# lin_master_node.net
KiCad netlist of a schematic drawn in EAGLE
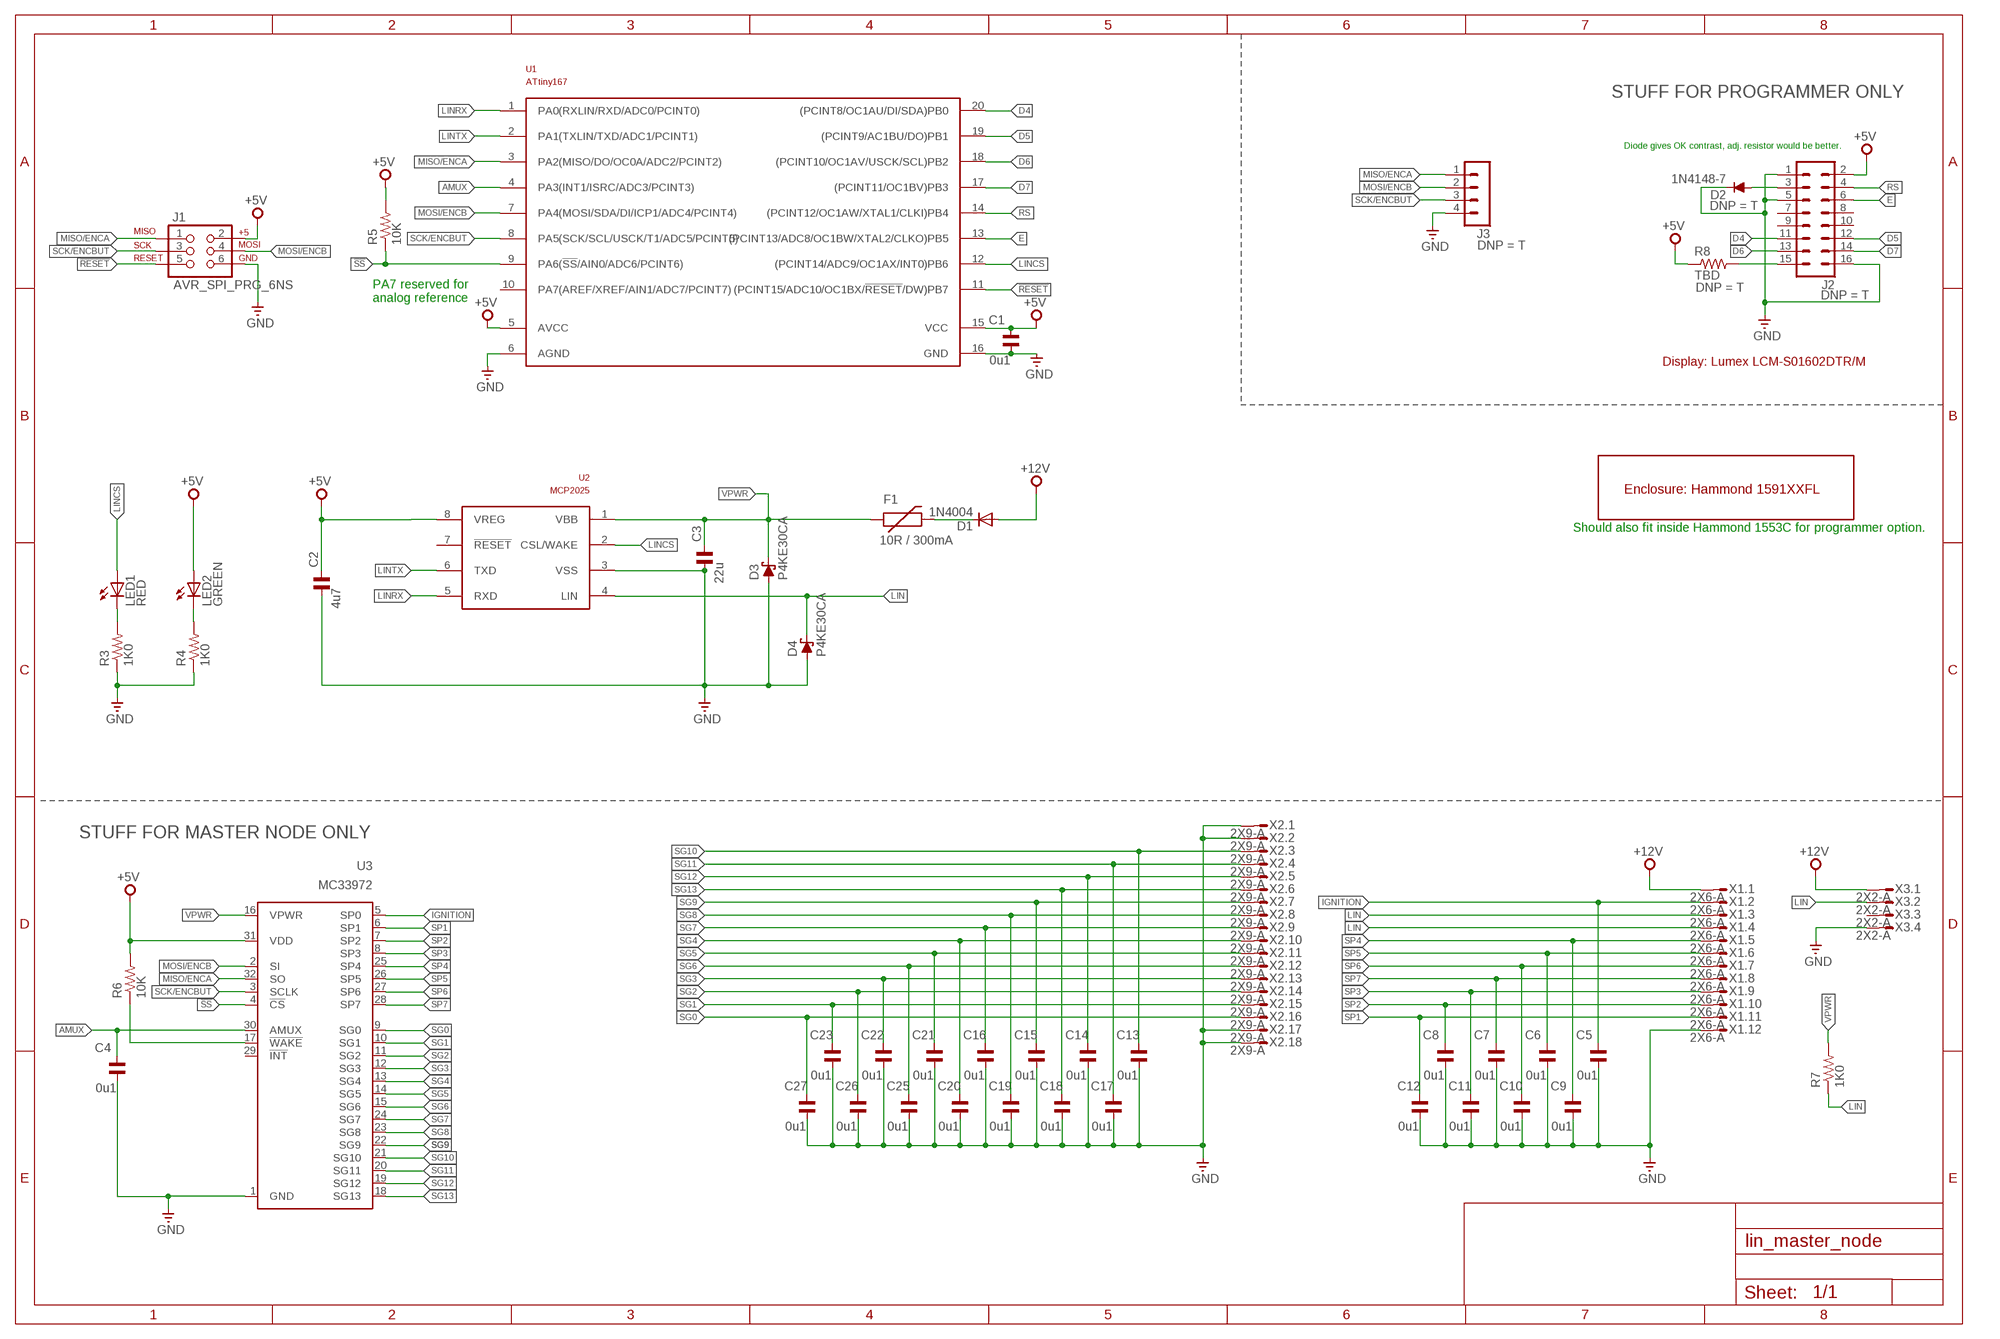
[diagram p0: schematic, sheet 1]

(export (version "E")
  (design (tool "Eeschema 10.0.6"))
  (components
    (comp (ref "C1")
      (value "0u1")
      (footprint "eagle-import:C050-024X044")
      (fields (field (name "PARTNO") "FK28X7R1H104K"))
      (libsource (lib "eagle-import") (part "C-EU050-024X044"))
    )
    (comp (ref "C2")
      (value "4u7")
      (footprint "eagle-import:C050-024X044")
      (fields (field (name "PARTNO") "FK28X5R0J475K"))
      (libsource (lib "eagle-import") (part "C-EU050-024X044"))
    )
    (comp (ref "C3")
      (value "22u")
      (footprint "eagle-import:C050-024X044")
      (fields (field (name "PARTNO") "FK22X5R1E226M"))
      (libsource (lib "eagle-import") (part "C-EU050-024X044"))
    )
    (comp (ref "C4")
      (value "0u1")
      (footprint "eagle-import:C050-024X044")
      (fields (field (name "PARTNO") "FK28X7R1H104K"))
      (libsource (lib "eagle-import") (part "C-EU050-024X044"))
    )
    (comp (ref "C5")
      (value "0u1")
      (footprint "eagle-import:C0603K")
      (fields (field (name "PARTNO") "C1608X7R1H104M080AA"))
      (libsource (lib "eagle-import") (part "C-EUC0603K"))
    )
    (comp (ref "C6")
      (value "0u1")
      (footprint "eagle-import:C0603K")
      (fields (field (name "PARTNO") "C1608X7R1H104M080AA"))
      (libsource (lib "eagle-import") (part "C-EUC0603K"))
    )
    (comp (ref "C7")
      (value "0u1")
      (footprint "eagle-import:C0603K")
      (fields (field (name "PARTNO") "C1608X7R1H104M080AA"))
      (libsource (lib "eagle-import") (part "C-EUC0603K"))
    )
    (comp (ref "C8")
      (value "0u1")
      (footprint "eagle-import:C0603K")
      (fields (field (name "PARTNO") "C1608X7R1H104M080AA"))
      (libsource (lib "eagle-import") (part "C-EUC0603K"))
    )
    (comp (ref "C9")
      (value "0u1")
      (footprint "eagle-import:C0603K")
      (fields (field (name "PARTNO") "C1608X7R1H104M080AA"))
      (libsource (lib "eagle-import") (part "C-EUC0603K"))
    )
    (comp (ref "C10")
      (value "0u1")
      (footprint "eagle-import:C0603K")
      (fields (field (name "PARTNO") "C1608X7R1H104M080AA"))
      (libsource (lib "eagle-import") (part "C-EUC0603K"))
    )
    (comp (ref "C11")
      (value "0u1")
      (footprint "eagle-import:C0603K")
      (fields (field (name "PARTNO") "C1608X7R1H104M080AA"))
      (libsource (lib "eagle-import") (part "C-EUC0603K"))
    )
    (comp (ref "C12")
      (value "0u1")
      (footprint "eagle-import:C0603K")
      (fields (field (name "PARTNO") "C1608X7R1H104M080AA"))
      (libsource (lib "eagle-import") (part "C-EUC0603K"))
    )
    (comp (ref "C13")
      (value "0u1")
      (footprint "eagle-import:C0603K")
      (fields (field (name "PARTNO") "C1608X7R1H104M080AA"))
      (libsource (lib "eagle-import") (part "C-EUC0603K"))
    )
    (comp (ref "C14")
      (value "0u1")
      (footprint "eagle-import:C0603K")
      (fields (field (name "PARTNO") "C1608X7R1H104M080AA"))
      (libsource (lib "eagle-import") (part "C-EUC0603K"))
    )
    (comp (ref "C15")
      (value "0u1")
      (footprint "eagle-import:C0603K")
      (fields (field (name "PARTNO") "C1608X7R1H104M080AA"))
      (libsource (lib "eagle-import") (part "C-EUC0603K"))
    )
    (comp (ref "C16")
      (value "0u1")
      (footprint "eagle-import:C0603K")
      (fields (field (name "PARTNO") "C1608X7R1H104M080AA"))
      (libsource (lib "eagle-import") (part "C-EUC0603K"))
    )
    (comp (ref "C17")
      (value "0u1")
      (footprint "eagle-import:C0603K")
      (fields (field (name "PARTNO") "C1608X7R1H104M080AA"))
      (libsource (lib "eagle-import") (part "C-EUC0603K"))
    )
    (comp (ref "C18")
      (value "0u1")
      (footprint "eagle-import:C0603K")
      (fields (field (name "PARTNO") "C1608X7R1H104M080AA"))
      (libsource (lib "eagle-import") (part "C-EUC0603K"))
    )
    (comp (ref "C19")
      (value "0u1")
      (footprint "eagle-import:C0603K")
      (fields (field (name "PARTNO") "C1608X7R1H104M080AA"))
      (libsource (lib "eagle-import") (part "C-EUC0603K"))
    )
    (comp (ref "C20")
      (value "0u1")
      (footprint "eagle-import:C0603K")
      (fields (field (name "PARTNO") "C1608X7R1H104M080AA"))
      (libsource (lib "eagle-import") (part "C-EUC0603K"))
    )
    (comp (ref "C21")
      (value "0u1")
      (footprint "eagle-import:C0603K")
      (fields (field (name "PARTNO") "C1608X7R1H104M080AA"))
      (libsource (lib "eagle-import") (part "C-EUC0603K"))
    )
    (comp (ref "C22")
      (value "0u1")
      (footprint "eagle-import:C0603K")
      (fields (field (name "PARTNO") "C1608X7R1H104M080AA"))
      (libsource (lib "eagle-import") (part "C-EUC0603K"))
    )
    (comp (ref "C23")
      (value "0u1")
      (footprint "eagle-import:C0603K")
      (fields (field (name "PARTNO") "C1608X7R1H104M080AA"))
      (libsource (lib "eagle-import") (part "C-EUC0603K"))
    )
    (comp (ref "C25")
      (value "0u1")
      (footprint "eagle-import:C0603K")
      (fields (field (name "PARTNO") "C1608X7R1H104M080AA"))
      (libsource (lib "eagle-import") (part "C-EUC0603K"))
    )
    (comp (ref "C26")
      (value "0u1")
      (footprint "eagle-import:C0603K")
      (fields (field (name "PARTNO") "C1608X7R1H104M080AA"))
      (libsource (lib "eagle-import") (part "C-EUC0603K"))
    )
    (comp (ref "C27")
      (value "0u1")
      (footprint "eagle-import:C0603K")
      (fields (field (name "PARTNO") "C1608X7R1H104M080AA"))
      (libsource (lib "eagle-import") (part "C-EUC0603K"))
    )
    (comp (ref "D1")
      (value "1N4004")
      (footprint "eagle-import:DO41-10")
      (fields (field (name "PARTNO") "1N4004-TP"))
      (libsource (lib "eagle-import") (part "1N4004"))
    )
    (comp (ref "D2")
      (value "1N4148-7")
      (footprint "eagle-import:DO35-7")
      (fields (field (name "DNP") "T") (field (name "PARTNO") "1N4148TA"))
      (libsource (lib "eagle-import") (part "1N4148-7"))
    )
    (comp (ref "D3")
      (value "P4KE30CA")
      (footprint "eagle-import:DO41-10")
      (libsource (lib "eagle-import") (part "P4KEXX"))
    )
    (comp (ref "D4")
      (value "P4KE30CA")
      (footprint "eagle-import:DO41-10")
      (libsource (lib "eagle-import") (part "P4KEXX"))
    )
    (comp (ref "F1")
      (value "10R / 300mA")
      (footprint "eagle-import:PTC")
      (fields (field (name "PARTNO") "CMF-RL10-0"))
      (libsource (lib "eagle-import") (part "PTCPTH"))
    )
    (comp (ref "J1")
      (value "AVR_SPI_PRG_6NS")
      (footprint "eagle-import:2X3-NS")
      (libsource (lib "eagle-import") (part "AVR_SPI_PRG_6NS"))
    )
    (comp (ref "J2")
      (value "MA08-2")
      (footprint "eagle-import:MA08-2")
      (fields (field (name "DNP") "T"))
      (libsource (lib "eagle-import") (part "MA08-2"))
    )
    (comp (ref "J3")
      (value "MA04-1")
      (footprint "eagle-import:MA04-1")
      (fields (field (name "DNP") "T"))
      (libsource (lib "eagle-import") (part "MA04-1"))
    )
    (comp (ref "LED1")
      (value "RED")
      (footprint "eagle-import:LED3MM")
      (fields (field (name "PARTNO") "C4SMF-RJS-CT0W0BB2"))
      (libsource (lib "eagle-import") (part "LED3MM"))
    )
    (comp (ref "LED2")
      (value "GREEN")
      (footprint "eagle-import:LED3MM")
      (fields (field (name "PARTNO") "C4SMF-GJS-CV0Y0792"))
      (libsource (lib "eagle-import") (part "LED3MM"))
    )
    (comp (ref "R3")
      (value "1K0")
      (footprint "eagle-import:0207_10")
      (fields (field (name "PARTNO") "CF14JT1K00"))
      (libsource (lib "eagle-import") (part "R-EU_0207/10"))
    )
    (comp (ref "R4")
      (value "1K0")
      (footprint "eagle-import:0207_10")
      (fields (field (name "PARTNO") "CF14JT1K00"))
      (libsource (lib "eagle-import") (part "R-EU_0207/10"))
    )
    (comp (ref "R5")
      (value "10K")
      (footprint "eagle-import:0207_10")
      (fields (field (name "PARTNO") "CF14JT10K0"))
      (libsource (lib "eagle-import") (part "R-EU_0207/10"))
    )
    (comp (ref "R6")
      (value "10K")
      (footprint "eagle-import:0207_10")
      (fields (field (name "PARTNO") "CF14JT10K0"))
      (libsource (lib "eagle-import") (part "R-EU_0207/10"))
    )
    (comp (ref "R7")
      (value "1K0")
      (footprint "eagle-import:0207_10")
      (fields (field (name "PARTNO") "CF14JT1K00"))
      (libsource (lib "eagle-import") (part "R-EU_0207/10"))
    )
    (comp (ref "R8")
      (value "TBD")
      (footprint "eagle-import:0207_10")
      (fields (field (name "DNP") "T"))
      (libsource (lib "eagle-import") (part "R-EU_0207/10"))
    )
    (comp (ref "U$1")
      (value "1591XXAFL")
      (footprint "eagle-import:1591XXAFL")
      (fields (field (name "PARTNO") "1591XXAFLBK"))
      (libsource (lib "eagle-import") (part "1591XXAFL"))
    )
    (comp (ref "U1")
      (value "ATtiny167")
      (footprint "eagle-import:SO20W")
      (fields (field (name "PARTNO") "ATTINY167-SU"))
      (libsource (lib "eagle-import") (part "ATTINY167"))
    )
    (comp (ref "U2")
      (value "MCP2025")
      (footprint "eagle-import:SO08")
      (fields (field (name "PARTNO") "MCP2025-500E/SN"))
      (libsource (lib "eagle-import") (part "MCP2025"))
    )
    (comp (ref "U3")
      (value "MC33972")
      (footprint "eagle-import:SOIC32W")
      (fields (field (name "PARTNO") "MC33972ATEW"))
      (libsource (lib "eagle-import") (part "MC33972"))
    )
    (comp (ref "X1")
      (value "2X6-A")
      (footprint "eagle-import:4-794618-2")
      (fields (field (name "PARTNO") "4-794618-2"))
      (libsource (lib "eagle-import") (part "2X6-A"))
    )
    (comp (ref "X2")
      (value "2X9-A")
      (footprint "eagle-import:4-794618-8")
      (fields (field (name "PARTNO") "4-794618-8"))
      (libsource (lib "eagle-import") (part "2X9-A"))
    )
    (comp (ref "X3")
      (value "2X2-A")
      (footprint "eagle-import:3-794618-4")
      (fields (field (name "PARTNO") "3-794618-4"))
      (libsource (lib "eagle-import") (part "2X2-A"))
    )
  )
  (nets
    (net (code "1") (name "+5V") (class "Default")
      (node (ref "C1") (pin "1") (pinfunction "1_1") (pintype "passive"))
      (node (ref "C2") (pin "1") (pinfunction "1_1") (pintype "passive"))
      (node (ref "J1") (pin "2") (pinfunction "2_2") (pintype "passive"))
      (node (ref "J2") (pin "2") (pinfunction "2_2") (pintype "passive"))
      (node (ref "LED2") (pin "A") (pinfunction "A_A") (pintype "passive"))
      (node (ref "R5") (pin "2") (pinfunction "2_2") (pintype "passive"))
      (node (ref "R6") (pin "2") (pinfunction "2_2") (pintype "passive"))
      (node (ref "R8") (pin "1") (pinfunction "1_1") (pintype "passive"))
      (node (ref "U1") (pin "15") (pinfunction "VCC_15") (pintype "power_in"))
      (node (ref "U1") (pin "5") (pinfunction "AVCC_5") (pintype "power_in"))
      (node (ref "U2") (pin "8") (pinfunction "VREG_8") (pintype "power_in"))
      (node (ref "U3") (pin "31") (pinfunction "VDD_31") (pintype "power_in"))
    )
    (net (code "2") (name "+12V") (class "Default")
      (node (ref "D1") (pin "A") (pinfunction "A_A") (pintype "passive"))
      (node (ref "X1") (pin "1") (pinfunction "S_1") (pintype "passive"))
      (node (ref "X3") (pin "1") (pinfunction "S_1") (pintype "passive"))
    )
    (net (code "3") (name "/~{RESET}") (class "Default")
      (node (ref "J1") (pin "5") (pinfunction "5_5") (pintype "passive"))
      (node (ref "U1") (pin "11") (pinfunction "(PCINT15/ADC10/OC1BX/~{RESET}/DW)PB7_11") (pintype "bidirectional"))
    )
    (net (code "4") (name "/~{SS}") (class "Default")
      (node (ref "R5") (pin "1") (pinfunction "1_1") (pintype "passive"))
      (node (ref "U1") (pin "9") (pinfunction "PA6(~{SS}/AIN0/ADC6/PCINT6)_9") (pintype "bidirectional"))
      (node (ref "U3") (pin "4") (pinfunction "~{CS}_4") (pintype "input"))
    )
    (net (code "5") (name "AMUX") (class "Default")
      (node (ref "C4") (pin "1") (pinfunction "1_1") (pintype "passive"))
      (node (ref "U1") (pin "4") (pinfunction "PA3(INT1/ISRC/ADC3/PCINT3)_4") (pintype "bidirectional"))
      (node (ref "U3") (pin "30") (pinfunction "AMUX_30") (pintype "output"))
    )
    (net (code "6") (name "D4") (class "Default")
      (node (ref "J2") (pin "11") (pinfunction "11_11") (pintype "passive"))
      (node (ref "U1") (pin "20") (pinfunction "(PCINT8/OC1AU/DI/SDA)PB0_20") (pintype "bidirectional"))
    )
    (net (code "7") (name "D5") (class "Default")
      (node (ref "J2") (pin "12") (pinfunction "12_12") (pintype "passive"))
      (node (ref "U1") (pin "19") (pinfunction "(PCINT9/AC1BU/DO)PB1_19") (pintype "bidirectional"))
    )
    (net (code "8") (name "D6") (class "Default")
      (node (ref "J2") (pin "13") (pinfunction "13_13") (pintype "passive"))
      (node (ref "U1") (pin "18") (pinfunction "(PCINT10/OC1AV/USCK/SCL)PB2_18") (pintype "bidirectional"))
    )
    (net (code "9") (name "D7") (class "Default")
      (node (ref "J2") (pin "14") (pinfunction "14_14") (pintype "passive"))
      (node (ref "U1") (pin "17") (pinfunction "(PCINT11/OC1BV)PB3_17") (pintype "bidirectional"))
    )
    (net (code "10") (name "E") (class "Default")
      (node (ref "J2") (pin "6") (pinfunction "6_6") (pintype "passive"))
      (node (ref "U1") (pin "13") (pinfunction "(PCINT13/ADC8/OC1BW/XTAL2/CLKO)PB5_13") (pintype "bidirectional"))
    )
    (net (code "11") (name "GND") (class "Default")
      (node (ref "C1") (pin "2") (pinfunction "2_2") (pintype "passive"))
      (node (ref "C10") (pin "2") (pinfunction "2_2") (pintype "passive"))
      (node (ref "C11") (pin "2") (pinfunction "2_2") (pintype "passive"))
      (node (ref "C12") (pin "2") (pinfunction "2_2") (pintype "passive"))
      (node (ref "C13") (pin "2") (pinfunction "2_2") (pintype "passive"))
      (node (ref "C14") (pin "2") (pinfunction "2_2") (pintype "passive"))
      (node (ref "C15") (pin "2") (pinfunction "2_2") (pintype "passive"))
      (node (ref "C16") (pin "2") (pinfunction "2_2") (pintype "passive"))
      (node (ref "C17") (pin "2") (pinfunction "2_2") (pintype "passive"))
      (node (ref "C18") (pin "2") (pinfunction "2_2") (pintype "passive"))
      (node (ref "C19") (pin "2") (pinfunction "2_2") (pintype "passive"))
      (node (ref "C2") (pin "2") (pinfunction "2_2") (pintype "passive"))
      (node (ref "C20") (pin "2") (pinfunction "2_2") (pintype "passive"))
      (node (ref "C21") (pin "2") (pinfunction "2_2") (pintype "passive"))
      (node (ref "C22") (pin "2") (pinfunction "2_2") (pintype "passive"))
      (node (ref "C23") (pin "2") (pinfunction "2_2") (pintype "passive"))
      (node (ref "C25") (pin "2") (pinfunction "2_2") (pintype "passive"))
      (node (ref "C26") (pin "2") (pinfunction "2_2") (pintype "passive"))
      (node (ref "C27") (pin "2") (pinfunction "2_2") (pintype "passive"))
      (node (ref "C3") (pin "2") (pinfunction "2_2") (pintype "passive"))
      (node (ref "C4") (pin "2") (pinfunction "2_2") (pintype "passive"))
      (node (ref "C5") (pin "2") (pinfunction "2_2") (pintype "passive"))
      (node (ref "C6") (pin "2") (pinfunction "2_2") (pintype "passive"))
      (node (ref "C7") (pin "2") (pinfunction "2_2") (pintype "passive"))
      (node (ref "C8") (pin "2") (pinfunction "2_2") (pintype "passive"))
      (node (ref "C9") (pin "2") (pinfunction "2_2") (pintype "passive"))
      (node (ref "D2") (pin "C") (pinfunction "C_C") (pintype "passive"))
      (node (ref "D3") (pin "A") (pinfunction "A_A") (pintype "passive"))
      (node (ref "D4") (pin "A") (pinfunction "A_A") (pintype "passive"))
      (node (ref "J1") (pin "6") (pinfunction "6_6") (pintype "passive"))
      (node (ref "J2") (pin "1") (pinfunction "1_1") (pintype "passive"))
      (node (ref "J2") (pin "16") (pinfunction "16_16") (pintype "passive"))
      (node (ref "J2") (pin "5") (pinfunction "5_5") (pintype "passive"))
      (node (ref "J3") (pin "4") (pinfunction "4_4") (pintype "passive"))
      (node (ref "R3") (pin "1") (pinfunction "1_1") (pintype "passive"))
      (node (ref "R4") (pin "1") (pinfunction "1_1") (pintype "passive"))
      (node (ref "U1") (pin "16") (pinfunction "GND_16") (pintype "power_in"))
      (node (ref "U1") (pin "6") (pinfunction "AGND_6") (pintype "power_in"))
      (node (ref "U2") (pin "3") (pinfunction "VSS_3") (pintype "power_in"))
      (node (ref "U3") (pin "1") (pinfunction "GND_1") (pintype "power_in"))
      (node (ref "X1") (pin "12") (pinfunction "S_12") (pintype "passive"))
      (node (ref "X2") (pin "1") (pinfunction "S_1") (pintype "passive"))
      (node (ref "X2") (pin "17") (pinfunction "S_17") (pintype "passive"))
      (node (ref "X2") (pin "18") (pinfunction "S_18") (pintype "passive"))
      (node (ref "X2") (pin "2") (pinfunction "S_2") (pintype "passive"))
      (node (ref "X3") (pin "4") (pinfunction "S_4") (pintype "passive"))
    )
    (net (code "12") (name "IGNITION") (class "Default")
      (node (ref "C5") (pin "1") (pinfunction "1_1") (pintype "passive"))
      (node (ref "U3") (pin "5") (pinfunction "SP0_5") (pintype "input"))
      (node (ref "X1") (pin "2") (pinfunction "S_2") (pintype "passive"))
    )
    (net (code "13") (name "LIN") (class "Default")
      (node (ref "D4") (pin "C") (pinfunction "C_C") (pintype "passive"))
      (node (ref "R7") (pin "1") (pinfunction "1_1") (pintype "passive"))
      (node (ref "U2") (pin "4") (pinfunction "LIN_4") (pintype "bidirectional"))
      (node (ref "X1") (pin "3") (pinfunction "S_3") (pintype "passive"))
      (node (ref "X1") (pin "4") (pinfunction "S_4") (pintype "passive"))
      (node (ref "X3") (pin "2") (pinfunction "S_2") (pintype "passive"))
    )
    (net (code "14") (name "LINCS") (class "Default")
      (node (ref "LED1") (pin "A") (pinfunction "A_A") (pintype "passive"))
      (node (ref "U1") (pin "12") (pinfunction "(PCINT14/ADC9/OC1AX/INT0)PB6_12") (pintype "bidirectional"))
      (node (ref "U2") (pin "2") (pinfunction "CSL/WAKE_2") (pintype "input"))
    )
    (net (code "15") (name "LINRX") (class "Default")
      (node (ref "U1") (pin "1") (pinfunction "PA0(RXLIN/RXD/ADC0/PCINT0)_1") (pintype "bidirectional"))
      (node (ref "U2") (pin "5") (pinfunction "RXD_5") (pintype "output"))
    )
    (net (code "16") (name "LINTX") (class "Default")
      (node (ref "U1") (pin "2") (pinfunction "PA1(TXLIN/TXD/ADC1/PCINT1)_2") (pintype "bidirectional"))
      (node (ref "U2") (pin "6") (pinfunction "TXD_6") (pintype "input"))
    )
    (net (code "17") (name "MISO{slash}ENCA") (class "Default")
      (node (ref "J1") (pin "1") (pinfunction "1_1") (pintype "passive"))
      (node (ref "J3") (pin "1") (pinfunction "1_1") (pintype "passive"))
      (node (ref "U1") (pin "3") (pinfunction "PA2(MISO/DO/OC0A/ADC2/PCINT2)_3") (pintype "bidirectional"))
      (node (ref "U3") (pin "32") (pinfunction "SO_32") (pintype "output"))
    )
    (net (code "18") (name "MOSI{slash}ENCB") (class "Default")
      (node (ref "J1") (pin "4") (pinfunction "4_4") (pintype "passive"))
      (node (ref "J3") (pin "2") (pinfunction "2_2") (pintype "passive"))
      (node (ref "U1") (pin "7") (pinfunction "PA4(MOSI/SDA/DI/ICP1/ADC4/PCINT4)_7") (pintype "bidirectional"))
      (node (ref "U3") (pin "2") (pinfunction "SI_2") (pintype "input"))
    )
    (net (code "19") (name "Net-(D2-PadA)") (class "Default")
      (node (ref "D2") (pin "A") (pinfunction "A_A") (pintype "passive"))
      (node (ref "J2") (pin "3") (pinfunction "3_3") (pintype "passive"))
    )
    (net (code "20") (name "Net-(F1-2)") (class "Default")
      (node (ref "D1") (pin "C") (pinfunction "C_C") (pintype "passive"))
      (node (ref "F1") (pin "P$2") (pinfunction "2_P$2") (pintype "bidirectional"))
    )
    (net (code "21") (name "Net-(J2-Pad15)") (class "Default")
      (node (ref "J2") (pin "15") (pinfunction "15_15") (pintype "passive"))
      (node (ref "R8") (pin "2") (pinfunction "2_2") (pintype "passive"))
    )
    (net (code "22") (name "Net-(LED1-C)") (class "Default")
      (node (ref "LED1") (pin "K") (pinfunction "C_K") (pintype "passive"))
      (node (ref "R3") (pin "2") (pinfunction "2_2") (pintype "passive"))
    )
    (net (code "23") (name "Net-(LED2-C)") (class "Default")
      (node (ref "LED2") (pin "K") (pinfunction "C_K") (pintype "passive"))
      (node (ref "R4") (pin "2") (pinfunction "2_2") (pintype "passive"))
    )
    (net (code "24") (name "Net-(U3-~{WAKE})") (class "Default")
      (node (ref "R6") (pin "1") (pinfunction "1_1") (pintype "passive"))
      (node (ref "U3") (pin "17") (pinfunction "~{WAKE}_17") (pintype "open_collector"))
    )
    (net (code "25") (name "RS") (class "Default")
      (node (ref "J2") (pin "4") (pinfunction "4_4") (pintype "passive"))
      (node (ref "U1") (pin "14") (pinfunction "(PCINT12/OC1AW/XTAL1/CLKI)PB4_14") (pintype "bidirectional"))
    )
    (net (code "26") (name "SCK{slash}ENCBUT") (class "Default")
      (node (ref "J1") (pin "3") (pinfunction "3_3") (pintype "passive"))
      (node (ref "J3") (pin "3") (pinfunction "3_3") (pintype "passive"))
      (node (ref "U1") (pin "8") (pinfunction "PA5(SCK/SCL/USCK/T1/ADC5/PCINT5)_8") (pintype "bidirectional"))
      (node (ref "U3") (pin "3") (pinfunction "SCLK_3") (pintype "input"))
    )
    (net (code "27") (name "SG0") (class "Default")
      (node (ref "C27") (pin "1") (pinfunction "1_1") (pintype "passive"))
      (node (ref "U3") (pin "9") (pinfunction "SG0_9") (pintype "input"))
      (node (ref "X2") (pin "16") (pinfunction "S_16") (pintype "passive"))
    )
    (net (code "28") (name "SG1") (class "Default")
      (node (ref "C23") (pin "1") (pinfunction "1_1") (pintype "passive"))
      (node (ref "U3") (pin "10") (pinfunction "SG1_10") (pintype "input"))
      (node (ref "X2") (pin "15") (pinfunction "S_15") (pintype "passive"))
    )
    (net (code "29") (name "SG2") (class "Default")
      (node (ref "C26") (pin "1") (pinfunction "1_1") (pintype "passive"))
      (node (ref "U3") (pin "11") (pinfunction "SG2_11") (pintype "input"))
      (node (ref "X2") (pin "14") (pinfunction "S_14") (pintype "passive"))
    )
    (net (code "30") (name "SG3") (class "Default")
      (node (ref "C22") (pin "1") (pinfunction "1_1") (pintype "passive"))
      (node (ref "U3") (pin "12") (pinfunction "SG3_12") (pintype "input"))
      (node (ref "X2") (pin "13") (pinfunction "S_13") (pintype "passive"))
    )
    (net (code "31") (name "SG4") (class "Default")
      (node (ref "C20") (pin "1") (pinfunction "1_1") (pintype "passive"))
      (node (ref "U3") (pin "13") (pinfunction "SG4_13") (pintype "input"))
      (node (ref "X2") (pin "10") (pinfunction "S_10") (pintype "passive"))
    )
    (net (code "32") (name "SG5") (class "Default")
      (node (ref "C21") (pin "1") (pinfunction "1_1") (pintype "passive"))
      (node (ref "U3") (pin "14") (pinfunction "SG5_14") (pintype "input"))
      (node (ref "X2") (pin "11") (pinfunction "S_11") (pintype "passive"))
    )
    (net (code "33") (name "SG6") (class "Default")
      (node (ref "C25") (pin "1") (pinfunction "1_1") (pintype "passive"))
      (node (ref "U3") (pin "15") (pinfunction "SG6_15") (pintype "input"))
      (node (ref "X2") (pin "12") (pinfunction "S_12") (pintype "passive"))
    )
    (net (code "34") (name "SG7") (class "Default")
      (node (ref "C16") (pin "1") (pinfunction "1_1") (pintype "passive"))
      (node (ref "U3") (pin "24") (pinfunction "SG7_24") (pintype "input"))
      (node (ref "X2") (pin "9") (pinfunction "S_9") (pintype "passive"))
    )
    (net (code "35") (name "SG8") (class "Default")
      (node (ref "C19") (pin "1") (pinfunction "1_1") (pintype "passive"))
      (node (ref "U3") (pin "23") (pinfunction "SG8_23") (pintype "input"))
      (node (ref "X2") (pin "8") (pinfunction "S_8") (pintype "passive"))
    )
    (net (code "36") (name "SG9") (class "Default")
      (node (ref "C15") (pin "1") (pinfunction "1_1") (pintype "passive"))
      (node (ref "U3") (pin "22") (pinfunction "SG9_22") (pintype "input"))
      (node (ref "X2") (pin "7") (pinfunction "S_7") (pintype "passive"))
    )
    (net (code "37") (name "SG10") (class "Default")
      (node (ref "C13") (pin "1") (pinfunction "1_1") (pintype "passive"))
      (node (ref "U3") (pin "21") (pinfunction "SG10_21") (pintype "input"))
      (node (ref "X2") (pin "3") (pinfunction "S_3") (pintype "passive"))
    )
    (net (code "38") (name "SG11") (class "Default")
      (node (ref "C17") (pin "1") (pinfunction "1_1") (pintype "passive"))
      (node (ref "U3") (pin "20") (pinfunction "SG11_20") (pintype "input"))
      (node (ref "X2") (pin "4") (pinfunction "S_4") (pintype "passive"))
    )
    (net (code "39") (name "SG12") (class "Default")
      (node (ref "C14") (pin "1") (pinfunction "1_1") (pintype "passive"))
      (node (ref "U3") (pin "19") (pinfunction "SG12_19") (pintype "input"))
      (node (ref "X2") (pin "5") (pinfunction "S_5") (pintype "passive"))
    )
    (net (code "40") (name "SG13") (class "Default")
      (node (ref "C18") (pin "1") (pinfunction "1_1") (pintype "passive"))
      (node (ref "U3") (pin "18") (pinfunction "SG13_18") (pintype "input"))
      (node (ref "X2") (pin "6") (pinfunction "S_6") (pintype "passive"))
    )
    (net (code "41") (name "SP1") (class "Default")
      (node (ref "C12") (pin "1") (pinfunction "1_1") (pintype "passive"))
      (node (ref "U3") (pin "6") (pinfunction "SP1_6") (pintype "input"))
      (node (ref "X1") (pin "11") (pinfunction "S_11") (pintype "passive"))
    )
    (net (code "42") (name "SP2") (class "Default")
      (node (ref "C8") (pin "1") (pinfunction "1_1") (pintype "passive"))
      (node (ref "U3") (pin "7") (pinfunction "SP2_7") (pintype "input"))
      (node (ref "X1") (pin "10") (pinfunction "S_10") (pintype "passive"))
    )
    (net (code "43") (name "SP3") (class "Default")
      (node (ref "C11") (pin "1") (pinfunction "1_1") (pintype "passive"))
      (node (ref "U3") (pin "8") (pinfunction "SP3_8") (pintype "input"))
      (node (ref "X1") (pin "9") (pinfunction "S_9") (pintype "passive"))
    )
    (net (code "44") (name "SP4") (class "Default")
      (node (ref "C9") (pin "1") (pinfunction "1_1") (pintype "passive"))
      (node (ref "U3") (pin "25") (pinfunction "SP4_25") (pintype "input"))
      (node (ref "X1") (pin "5") (pinfunction "S_5") (pintype "passive"))
    )
    (net (code "45") (name "SP5") (class "Default")
      (node (ref "C6") (pin "1") (pinfunction "1_1") (pintype "passive"))
      (node (ref "U3") (pin "26") (pinfunction "SP5_26") (pintype "input"))
      (node (ref "X1") (pin "6") (pinfunction "S_6") (pintype "passive"))
    )
    (net (code "46") (name "SP6") (class "Default")
      (node (ref "C10") (pin "1") (pinfunction "1_1") (pintype "passive"))
      (node (ref "U3") (pin "27") (pinfunction "SP6_27") (pintype "input"))
      (node (ref "X1") (pin "7") (pinfunction "S_7") (pintype "passive"))
    )
    (net (code "47") (name "SP7") (class "Default")
      (node (ref "C7") (pin "1") (pinfunction "1_1") (pintype "passive"))
      (node (ref "U3") (pin "28") (pinfunction "SP7_28") (pintype "input"))
      (node (ref "X1") (pin "8") (pinfunction "S_8") (pintype "passive"))
    )
    (net (code "48") (name "VPWR") (class "Default")
      (node (ref "C3") (pin "1") (pinfunction "1_1") (pintype "passive"))
      (node (ref "D3") (pin "C") (pinfunction "C_C") (pintype "passive"))
      (node (ref "F1") (pin "P$1") (pinfunction "1_P$1") (pintype "bidirectional"))
      (node (ref "R7") (pin "2") (pinfunction "2_2") (pintype "passive"))
      (node (ref "U2") (pin "1") (pinfunction "VBB_1") (pintype "power_in"))
      (node (ref "U3") (pin "16") (pinfunction "VPWR_16") (pintype "power_in"))
    )
    (net (code "49") (name "unconnected-(J2-Pad7)") (class "Default")
      (node (ref "J2") (pin "7") (pinfunction "7_7") (pintype "passive"))
    )
    (net (code "50") (name "unconnected-(J2-Pad8)") (class "Default")
      (node (ref "J2") (pin "8") (pinfunction "8_8") (pintype "passive"))
    )
    (net (code "51") (name "unconnected-(J2-Pad9)") (class "Default")
      (node (ref "J2") (pin "9") (pinfunction "9_9") (pintype "passive"))
    )
    (net (code "52") (name "unconnected-(J2-Pad10)") (class "Default")
      (node (ref "J2") (pin "10") (pinfunction "10_10") (pintype "passive"))
    )
    (net (code "53") (name "unconnected-(U1-PA7(AREF{slash}XREF{slash}AIN1{slash}ADC7{slash}PCINT7)-Pad10)") (class "Default")
      (node (ref "U1") (pin "10") (pinfunction "PA7(AREF/XREF/AIN1/ADC7/PCINT7)_10") (pintype "bidirectional"))
    )
    (net (code "54") (name "unconnected-(U2-~{RESET}-Pad7)") (class "Default")
      (node (ref "U2") (pin "7") (pinfunction "~{RESET}_7") (pintype "open_collector"))
    )
    (net (code "55") (name "unconnected-(U3-~{INT}-Pad29)") (class "Default")
      (node (ref "U3") (pin "29") (pinfunction "~{INT}_29") (pintype "open_collector"))
    )
    (net (code "56") (name "unconnected-(X3C-S-Pad3)") (class "Default")
      (node (ref "X3") (pin "3") (pinfunction "S_3") (pintype "passive"))
    )
  )
)
